# Led_Circle.net
KiCad netlist of a schematic drawn in EAGLE
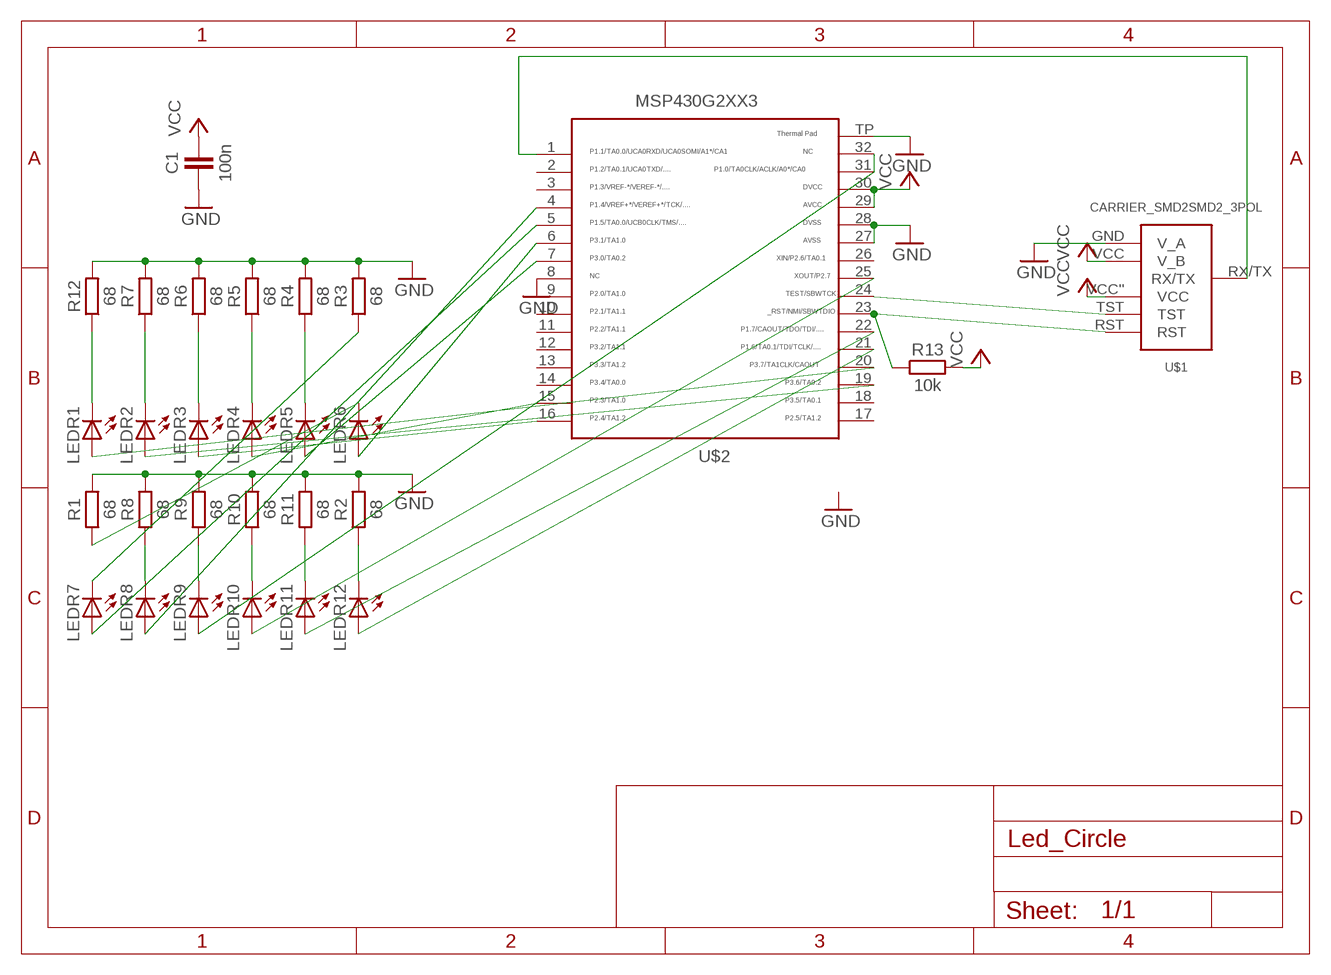
[diagram p0: schematic, sheet 1]

(export (version "E")
  (design (tool "Eeschema 10.0.6"))
  (components
    (comp (ref "C1")
      (value "100n")
      (footprint "eagle-import:603")
      (libsource (lib "eagle-import") (part "CAPACITOR"))
    )
    (comp (ref "LEDR1")
      (value "LEDCHIPLED_0603")
      (footprint "eagle-import:CHIPLED_0603")
      (libsource (lib "eagle-import") (part "LEDCHIPLED_0603"))
    )
    (comp (ref "LEDR2")
      (value "LEDCHIPLED_0603")
      (footprint "eagle-import:CHIPLED_0603")
      (libsource (lib "eagle-import") (part "LEDCHIPLED_0603"))
    )
    (comp (ref "LEDR3")
      (value "LEDCHIPLED_0603")
      (footprint "eagle-import:CHIPLED_0603")
      (libsource (lib "eagle-import") (part "LEDCHIPLED_0603"))
    )
    (comp (ref "LEDR4")
      (value "LEDCHIPLED_0603")
      (footprint "eagle-import:CHIPLED_0603")
      (libsource (lib "eagle-import") (part "LEDCHIPLED_0603"))
    )
    (comp (ref "LEDR5")
      (value "LEDCHIPLED_0603")
      (footprint "eagle-import:CHIPLED_0603")
      (libsource (lib "eagle-import") (part "LEDCHIPLED_0603"))
    )
    (comp (ref "LEDR6")
      (value "LEDCHIPLED_0603")
      (footprint "eagle-import:CHIPLED_0603")
      (libsource (lib "eagle-import") (part "LEDCHIPLED_0603"))
    )
    (comp (ref "LEDR7")
      (value "LEDCHIPLED_0603")
      (footprint "eagle-import:CHIPLED_0603")
      (libsource (lib "eagle-import") (part "LEDCHIPLED_0603"))
    )
    (comp (ref "LEDR8")
      (value "LEDCHIPLED_0603")
      (footprint "eagle-import:CHIPLED_0603")
      (libsource (lib "eagle-import") (part "LEDCHIPLED_0603"))
    )
    (comp (ref "LEDR9")
      (value "LEDCHIPLED_0603")
      (footprint "eagle-import:CHIPLED_0603")
      (libsource (lib "eagle-import") (part "LEDCHIPLED_0603"))
    )
    (comp (ref "LEDR10")
      (value "LEDCHIPLED_0603")
      (footprint "eagle-import:CHIPLED_0603")
      (libsource (lib "eagle-import") (part "LEDCHIPLED_0603"))
    )
    (comp (ref "LEDR11")
      (value "LEDCHIPLED_0603")
      (footprint "eagle-import:CHIPLED_0603")
      (libsource (lib "eagle-import") (part "LEDCHIPLED_0603"))
    )
    (comp (ref "LEDR12")
      (value "LEDCHIPLED_0603")
      (footprint "eagle-import:CHIPLED_0603")
      (libsource (lib "eagle-import") (part "LEDCHIPLED_0603"))
    )
    (comp (ref "R1")
      (value "68")
      (footprint "eagle-import:603")
      (libsource (lib "eagle-import") (part "RESISTOR0603"))
    )
    (comp (ref "R2")
      (value "68")
      (footprint "eagle-import:603")
      (libsource (lib "eagle-import") (part "RESISTOR0603"))
    )
    (comp (ref "R3")
      (value "68")
      (footprint "eagle-import:603")
      (libsource (lib "eagle-import") (part "RESISTOR0603"))
    )
    (comp (ref "R4")
      (value "68")
      (footprint "eagle-import:603")
      (libsource (lib "eagle-import") (part "RESISTOR0603"))
    )
    (comp (ref "R5")
      (value "68")
      (footprint "eagle-import:603")
      (libsource (lib "eagle-import") (part "RESISTOR0603"))
    )
    (comp (ref "R6")
      (value "68")
      (footprint "eagle-import:603")
      (libsource (lib "eagle-import") (part "RESISTOR0603"))
    )
    (comp (ref "R7")
      (value "68")
      (footprint "eagle-import:603")
      (libsource (lib "eagle-import") (part "RESISTOR0603"))
    )
    (comp (ref "R8")
      (value "68")
      (footprint "eagle-import:603")
      (libsource (lib "eagle-import") (part "RESISTOR0603"))
    )
    (comp (ref "R9")
      (value "68")
      (footprint "eagle-import:603")
      (libsource (lib "eagle-import") (part "RESISTOR0603"))
    )
    (comp (ref "R10")
      (value "68")
      (footprint "eagle-import:603")
      (libsource (lib "eagle-import") (part "RESISTOR0603"))
    )
    (comp (ref "R11")
      (value "68")
      (footprint "eagle-import:603")
      (libsource (lib "eagle-import") (part "RESISTOR0603"))
    )
    (comp (ref "R12")
      (value "68")
      (footprint "eagle-import:603")
      (libsource (lib "eagle-import") (part "RESISTOR0603"))
    )
    (comp (ref "R13")
      (value "10k")
      (footprint "eagle-import:603")
      (libsource (lib "eagle-import") (part "RESISTOR0603"))
    )
    (comp (ref "U$1")
      (value "CARRIER_SMD2SMD2_3POL")
      (footprint "eagle-import:CARRIER_SMD2_3POL")
      (libsource (lib "eagle-import") (part "CARRIER_SMD2SMD2_3POL"))
    )
    (comp (ref "U$2")
      (value "MSP430G2553")
      (footprint "eagle-import:QFN32")
      (libsource (lib "eagle-import") (part "MSP430G2553"))
    )
  )
  (nets
    (net (code "1") (name "GND") (class "Default")
      (node (ref "C1") (pin "1") (pinfunction "1_1") (pintype "passive"))
      (node (ref "R1") (pin "2") (pinfunction "2_2") (pintype "passive"))
      (node (ref "R10") (pin "2") (pinfunction "2_2") (pintype "passive"))
      (node (ref "R11") (pin "2") (pinfunction "2_2") (pintype "passive"))
      (node (ref "R12") (pin "2") (pinfunction "2_2") (pintype "passive"))
      (node (ref "R2") (pin "2") (pinfunction "2_2") (pintype "passive"))
      (node (ref "R3") (pin "2") (pinfunction "2_2") (pintype "passive"))
      (node (ref "R4") (pin "2") (pinfunction "2_2") (pintype "passive"))
      (node (ref "R5") (pin "2") (pinfunction "2_2") (pintype "passive"))
      (node (ref "R6") (pin "2") (pinfunction "2_2") (pintype "passive"))
      (node (ref "R7") (pin "2") (pinfunction "2_2") (pintype "passive"))
      (node (ref "R8") (pin "2") (pinfunction "2_2") (pintype "passive"))
      (node (ref "R9") (pin "2") (pinfunction "2_2") (pintype "passive"))
      (node (ref "U$1") (pin "GND") (pinfunction "V_A_GND") (pintype "bidirectional"))
      (node (ref "U$2") (pin "27") (pinfunction "27_27") (pintype "bidirectional"))
      (node (ref "U$2") (pin "28") (pinfunction "28_28") (pintype "bidirectional"))
      (node (ref "U$2") (pin "8") (pinfunction "8_8") (pintype "bidirectional"))
      (node (ref "U$2") (pin "TP") (pinfunction "TP_TP") (pintype "bidirectional"))
    )
    (net (code "2") (name "Net-(LEDR1-PadA)") (class "Default")
      (node (ref "LEDR1") (pin "A") (pinfunction "A_A") (pintype "passive"))
      (node (ref "U$2") (pin "20") (pinfunction "20_20") (pintype "bidirectional"))
    )
    (net (code "3") (name "Net-(LEDR1-PadC)") (class "Default")
      (node (ref "LEDR1") (pin "C") (pinfunction "C_C") (pintype "passive"))
      (node (ref "R12") (pin "1") (pinfunction "1_1") (pintype "passive"))
    )
    (net (code "4") (name "Net-(LEDR2-PadA)") (class "Default")
      (node (ref "LEDR2") (pin "A") (pinfunction "A_A") (pintype "passive"))
      (node (ref "U$2") (pin "19") (pinfunction "19_19") (pintype "bidirectional"))
    )
    (net (code "5") (name "Net-(LEDR2-PadC)") (class "Default")
      (node (ref "LEDR2") (pin "C") (pinfunction "C_C") (pintype "passive"))
      (node (ref "R7") (pin "1") (pinfunction "1_1") (pintype "passive"))
    )
    (net (code "6") (name "Net-(LEDR3-PadA)") (class "Default")
      (node (ref "LEDR3") (pin "A") (pinfunction "A_A") (pintype "passive"))
      (node (ref "U$2") (pin "16") (pinfunction "16_16") (pintype "bidirectional"))
    )
    (net (code "7") (name "Net-(LEDR3-PadC)") (class "Default")
      (node (ref "LEDR3") (pin "C") (pinfunction "C_C") (pintype "passive"))
      (node (ref "R6") (pin "1") (pinfunction "1_1") (pintype "passive"))
    )
    (net (code "8") (name "Net-(LEDR4-PadA)") (class "Default")
      (node (ref "LEDR4") (pin "A") (pinfunction "A_A") (pintype "passive"))
      (node (ref "U$2") (pin "15") (pinfunction "15_15") (pintype "bidirectional"))
    )
    (net (code "9") (name "Net-(LEDR4-PadC)") (class "Default")
      (node (ref "LEDR4") (pin "C") (pinfunction "C_C") (pintype "passive"))
      (node (ref "R5") (pin "1") (pinfunction "1_1") (pintype "passive"))
    )
    (net (code "10") (name "Net-(LEDR5-PadA)") (class "Default")
      (node (ref "LEDR5") (pin "A") (pinfunction "A_A") (pintype "passive"))
      (node (ref "U$2") (pin "7") (pinfunction "7_7") (pintype "bidirectional"))
    )
    (net (code "11") (name "Net-(LEDR5-PadC)") (class "Default")
      (node (ref "LEDR5") (pin "C") (pinfunction "C_C") (pintype "passive"))
      (node (ref "R4") (pin "1") (pinfunction "1_1") (pintype "passive"))
    )
    (net (code "12") (name "Net-(LEDR6-PadA)") (class "Default")
      (node (ref "LEDR6") (pin "A") (pinfunction "A_A") (pintype "passive"))
      (node (ref "U$2") (pin "6") (pinfunction "6_6") (pintype "bidirectional"))
    )
    (net (code "13") (name "Net-(LEDR6-PadC)") (class "Default")
      (node (ref "LEDR6") (pin "C") (pinfunction "C_C") (pintype "passive"))
      (node (ref "R1") (pin "1") (pinfunction "1_1") (pintype "passive"))
    )
    (net (code "14") (name "Net-(LEDR7-PadA)") (class "Default")
      (node (ref "LEDR7") (pin "A") (pinfunction "A_A") (pintype "passive"))
      (node (ref "U$2") (pin "5") (pinfunction "5_5") (pintype "bidirectional"))
    )
    (net (code "15") (name "Net-(LEDR7-PadC)") (class "Default")
      (node (ref "LEDR7") (pin "C") (pinfunction "C_C") (pintype "passive"))
      (node (ref "R3") (pin "1") (pinfunction "1_1") (pintype "passive"))
    )
    (net (code "16") (name "Net-(LEDR8-PadA)") (class "Default")
      (node (ref "LEDR8") (pin "A") (pinfunction "A_A") (pintype "passive"))
      (node (ref "U$2") (pin "4") (pinfunction "4_4") (pintype "bidirectional"))
    )
    (net (code "17") (name "Net-(LEDR8-PadC)") (class "Default")
      (node (ref "LEDR8") (pin "C") (pinfunction "C_C") (pintype "passive"))
      (node (ref "R8") (pin "1") (pinfunction "1_1") (pintype "passive"))
    )
    (net (code "18") (name "Net-(LEDR9-PadA)") (class "Default")
      (node (ref "LEDR9") (pin "A") (pinfunction "A_A") (pintype "passive"))
      (node (ref "U$2") (pin "31") (pinfunction "31_31") (pintype "bidirectional"))
      (node (ref "U$2") (pin "32") (pinfunction "32_32") (pintype "bidirectional"))
    )
    (net (code "19") (name "Net-(LEDR9-PadC)") (class "Default")
      (node (ref "LEDR9") (pin "C") (pinfunction "C_C") (pintype "passive"))
      (node (ref "R9") (pin "1") (pinfunction "1_1") (pintype "passive"))
    )
    (net (code "20") (name "Net-(LEDR10-PadA)") (class "Default")
      (node (ref "LEDR10") (pin "A") (pinfunction "A_A") (pintype "passive"))
      (node (ref "U$2") (pin "25") (pinfunction "25_25") (pintype "bidirectional"))
    )
    (net (code "21") (name "Net-(LEDR10-PadC)") (class "Default")
      (node (ref "LEDR10") (pin "C") (pinfunction "C_C") (pintype "passive"))
      (node (ref "R10") (pin "1") (pinfunction "1_1") (pintype "passive"))
    )
    (net (code "22") (name "Net-(LEDR11-PadA)") (class "Default")
      (node (ref "LEDR11") (pin "A") (pinfunction "A_A") (pintype "passive"))
      (node (ref "U$2") (pin "22") (pinfunction "22_22") (pintype "bidirectional"))
    )
    (net (code "23") (name "Net-(LEDR11-PadC)") (class "Default")
      (node (ref "LEDR11") (pin "C") (pinfunction "C_C") (pintype "passive"))
      (node (ref "R11") (pin "1") (pinfunction "1_1") (pintype "passive"))
    )
    (net (code "24") (name "Net-(LEDR12-PadA)") (class "Default")
      (node (ref "LEDR12") (pin "A") (pinfunction "A_A") (pintype "passive"))
      (node (ref "U$2") (pin "21") (pinfunction "21_21") (pintype "bidirectional"))
    )
    (net (code "25") (name "Net-(LEDR12-PadC)") (class "Default")
      (node (ref "LEDR12") (pin "C") (pinfunction "C_C") (pintype "passive"))
      (node (ref "R2") (pin "1") (pinfunction "1_1") (pintype "passive"))
    )
    (net (code "26") (name "Net-(R13-Pad1)") (class "Default")
      (node (ref "R13") (pin "1") (pinfunction "1_1") (pintype "passive"))
      (node (ref "U$1") (pin "RST") (pinfunction "RST_RST") (pintype "bidirectional"))
      (node (ref "U$2") (pin "23") (pinfunction "23_23") (pintype "bidirectional"))
    )
    (net (code "27") (name "Net-(U$1-PadRX{slash}TX)") (class "Default")
      (node (ref "U$1") (pin "RX/TX") (pinfunction "RX/TX_RX/TX") (pintype "bidirectional"))
      (node (ref "U$2") (pin "1") (pinfunction "1_1") (pintype "bidirectional"))
    )
    (net (code "28") (name "Net-(U$1-PadTST)") (class "Default")
      (node (ref "U$1") (pin "TST") (pinfunction "TST_TST") (pintype "bidirectional"))
      (node (ref "U$2") (pin "24") (pinfunction "24_24") (pintype "bidirectional"))
    )
    (net (code "29") (name "VCC") (class "Default")
      (node (ref "C1") (pin "2") (pinfunction "2_2") (pintype "passive"))
      (node (ref "R13") (pin "2") (pinfunction "2_2") (pintype "passive"))
      (node (ref "U$1") (pin "VCC") (pinfunction "V_B_VCC") (pintype "bidirectional"))
      (node (ref "U$1") (pin "VCC''") (pinfunction "VCC_VCC''") (pintype "bidirectional"))
      (node (ref "U$2") (pin "29") (pinfunction "29_29") (pintype "bidirectional"))
      (node (ref "U$2") (pin "30") (pinfunction "30_30") (pintype "bidirectional"))
    )
    (net (code "30") (name "unconnected-(U$2-Pad2)") (class "Default")
      (node (ref "U$2") (pin "2") (pinfunction "2_2") (pintype "bidirectional"))
    )
    (net (code "31") (name "unconnected-(U$2-Pad3)") (class "Default")
      (node (ref "U$2") (pin "3") (pinfunction "3_3") (pintype "bidirectional"))
    )
    (net (code "32") (name "unconnected-(U$2-Pad9)") (class "Default")
      (node (ref "U$2") (pin "9") (pinfunction "9_9") (pintype "bidirectional"))
    )
    (net (code "33") (name "unconnected-(U$2-Pad10)") (class "Default")
      (node (ref "U$2") (pin "10") (pinfunction "10_10") (pintype "bidirectional"))
    )
    (net (code "34") (name "unconnected-(U$2-Pad11)") (class "Default")
      (node (ref "U$2") (pin "11") (pinfunction "11_11") (pintype "bidirectional"))
    )
    (net (code "35") (name "unconnected-(U$2-Pad12)") (class "Default")
      (node (ref "U$2") (pin "12") (pinfunction "12_12") (pintype "bidirectional"))
    )
    (net (code "36") (name "unconnected-(U$2-Pad13)") (class "Default")
      (node (ref "U$2") (pin "13") (pinfunction "13_13") (pintype "bidirectional"))
    )
    (net (code "37") (name "unconnected-(U$2-Pad14)") (class "Default")
      (node (ref "U$2") (pin "14") (pinfunction "14_14") (pintype "bidirectional"))
    )
    (net (code "38") (name "unconnected-(U$2-Pad17)") (class "Default")
      (node (ref "U$2") (pin "17") (pinfunction "17_17") (pintype "bidirectional"))
    )
    (net (code "39") (name "unconnected-(U$2-Pad18)") (class "Default")
      (node (ref "U$2") (pin "18") (pinfunction "18_18") (pintype "bidirectional"))
    )
    (net (code "40") (name "unconnected-(U$2-Pad26)") (class "Default")
      (node (ref "U$2") (pin "26") (pinfunction "26_26") (pintype "bidirectional"))
    )
  )
)
